# interface_b.net
KiCad netlist of a schematic drawn in EAGLE
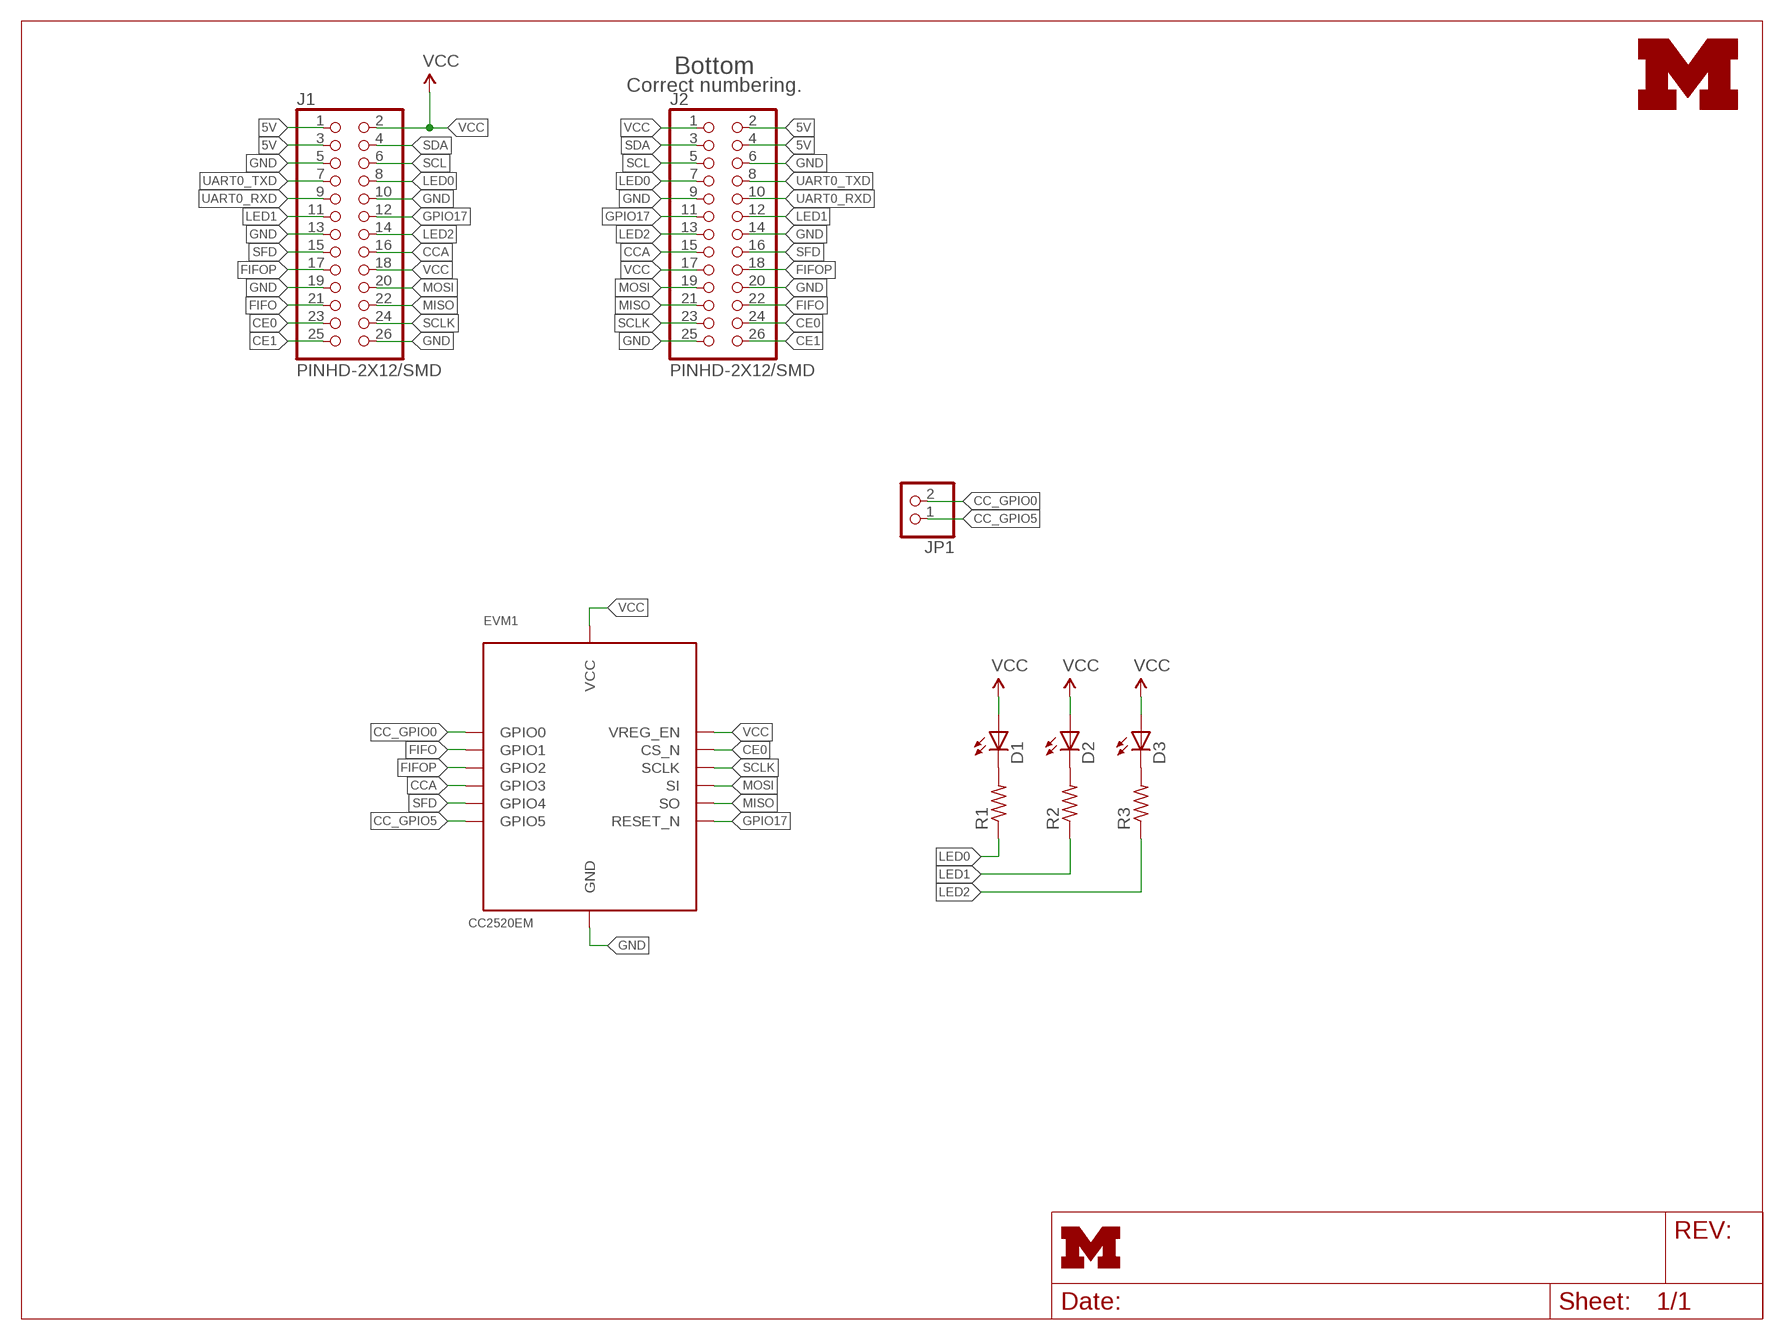
[diagram p0: schematic, sheet 1]

(export (version "E")
  (design (tool "Eeschema 10.0.6"))
  (components
    (comp (ref "D1")
      (value "LED0603")
      (footprint "eagle-import:LED-0603")
      (libsource (lib "eagle-import") (part "LED0603"))
    )
    (comp (ref "D2")
      (value "LED0603")
      (footprint "eagle-import:LED-0603")
      (libsource (lib "eagle-import") (part "LED0603"))
    )
    (comp (ref "D3")
      (value "LED0603")
      (footprint "eagle-import:LED-0603")
      (libsource (lib "eagle-import") (part "LED0603"))
    )
    (comp (ref "EVM1")
      (value "CC2520EM")
      (footprint "eagle-import:TI_CC_EVM")
      (libsource (lib "eagle-import") (part "CC2520EM"))
    )
    (comp (ref "J1")
      (value "PINHD-2X12/SMD")
      (footprint "eagle-import:2X13_SMD")
      (libsource (lib "eagle-import") (part "PINHD-2X12/SMD"))
    )
    (comp (ref "J2")
      (value "PINHD-2X12/SMD")
      (footprint "eagle-import:2X13_SMD")
      (libsource (lib "eagle-import") (part "PINHD-2X12/SMD"))
    )
    (comp (ref "JP1")
      (value "PINHD-1X2")
      (footprint "eagle-import:1X02")
      (libsource (lib "eagle-import") (part "PINHD-1X2"))
    )
    (comp (ref "R1")
      (value "R-US_R0603")
      (footprint "eagle-import:R0603")
      (libsource (lib "eagle-import") (part "R-US_R0603"))
    )
    (comp (ref "R2")
      (value "R-US_R0603")
      (footprint "eagle-import:R0603")
      (libsource (lib "eagle-import") (part "R-US_R0603"))
    )
    (comp (ref "R3")
      (value "R-US_R0603")
      (footprint "eagle-import:R0603")
      (libsource (lib "eagle-import") (part "R-US_R0603"))
    )
    (comp (ref "U$1")
      (value "UMICH_SOLID_SMALL")
      (footprint "eagle-import:UMICH_SOLID_75MIL")
      (libsource (lib "eagle-import") (part "UMICH_SOLID_SMALL"))
    )
  )
  (nets
    (net (code "1") (name "5V") (class "Default")
      (node (ref "J1") (pin "1") (pinfunction "1_1") (pintype "passive"))
      (node (ref "J1") (pin "3") (pinfunction "3_3") (pintype "passive"))
      (node (ref "J2") (pin "2") (pinfunction "2_2") (pintype "passive"))
      (node (ref "J2") (pin "4") (pinfunction "4_4") (pintype "passive"))
    )
    (net (code "2") (name "CCA") (class "Default")
      (node (ref "EVM1") (pin "P1_12") (pinfunction "GPIO3_P1_12") (pintype "bidirectional"))
      (node (ref "J1") (pin "16") (pinfunction "16_16") (pintype "passive"))
      (node (ref "J2") (pin "15") (pinfunction "15_15") (pintype "passive"))
    )
    (net (code "3") (name "CC_GPIO0") (class "Default")
      (node (ref "EVM1") (pin "P1_3") (pinfunction "GPIO0_P1_3") (pintype "bidirectional"))
      (node (ref "JP1") (pin "2") (pinfunction "2_2") (pintype "passive"))
    )
    (net (code "4") (name "CC_GPIO5") (class "Default")
      (node (ref "EVM1") (pin "P2_19") (pinfunction "GPIO5_P2_19") (pintype "bidirectional"))
      (node (ref "JP1") (pin "1") (pinfunction "1_1") (pintype "passive"))
    )
    (net (code "5") (name "CE0") (class "Default")
      (node (ref "EVM1") (pin "P1_14") (pinfunction "CS_N_P1_14") (pintype "bidirectional"))
      (node (ref "J1") (pin "23") (pinfunction "23_23") (pintype "passive"))
      (node (ref "J2") (pin "24") (pinfunction "24_24") (pintype "passive"))
    )
    (net (code "6") (name "CE1") (class "Default")
      (node (ref "J1") (pin "25") (pinfunction "25_25") (pintype "passive"))
      (node (ref "J2") (pin "26") (pinfunction "26_26") (pintype "passive"))
    )
    (net (code "7") (name "FIFO") (class "Default")
      (node (ref "EVM1") (pin "P1_7") (pinfunction "GPIO1_P1_7") (pintype "bidirectional"))
      (node (ref "J1") (pin "21") (pinfunction "21_21") (pintype "passive"))
      (node (ref "J2") (pin "22") (pinfunction "22_22") (pintype "passive"))
    )
    (net (code "8") (name "FIFOP") (class "Default")
      (node (ref "EVM1") (pin "P1_9") (pinfunction "GPIO2_P1_9") (pintype "bidirectional"))
      (node (ref "J1") (pin "17") (pinfunction "17_17") (pintype "passive"))
      (node (ref "J2") (pin "18") (pinfunction "18_18") (pintype "passive"))
    )
    (net (code "9") (name "GND") (class "Default")
      (node (ref "EVM1") (pin "P1_1") (pinfunction "GND_P1_1") (pintype "bidirectional"))
      (node (ref "EVM1") (pin "P1_19") (pinfunction "GND_P1_19") (pintype "bidirectional"))
      (node (ref "J1") (pin "10") (pinfunction "10_10") (pintype "passive"))
      (node (ref "J1") (pin "13") (pinfunction "13_13") (pintype "passive"))
      (node (ref "J1") (pin "19") (pinfunction "19_19") (pintype "passive"))
      (node (ref "J1") (pin "26") (pinfunction "26_26") (pintype "passive"))
      (node (ref "J1") (pin "5") (pinfunction "5_5") (pintype "passive"))
      (node (ref "J2") (pin "14") (pinfunction "14_14") (pintype "passive"))
      (node (ref "J2") (pin "20") (pinfunction "20_20") (pintype "passive"))
      (node (ref "J2") (pin "25") (pinfunction "25_25") (pintype "passive"))
      (node (ref "J2") (pin "6") (pinfunction "6_6") (pintype "passive"))
      (node (ref "J2") (pin "9") (pinfunction "9_9") (pintype "passive"))
    )
    (net (code "10") (name "GPIO17") (class "Default")
      (node (ref "EVM1") (pin "P2_15") (pinfunction "RESET_N_P2_15") (pintype "bidirectional"))
      (node (ref "J1") (pin "12") (pinfunction "12_12") (pintype "passive"))
      (node (ref "J2") (pin "11") (pinfunction "11_11") (pintype "passive"))
    )
    (net (code "11") (name "LED0") (class "Default")
      (node (ref "J1") (pin "8") (pinfunction "8_8") (pintype "passive"))
      (node (ref "J2") (pin "7") (pinfunction "7_7") (pintype "passive"))
      (node (ref "R1") (pin "1") (pinfunction "1_1") (pintype "passive"))
    )
    (net (code "12") (name "LED1") (class "Default")
      (node (ref "J1") (pin "11") (pinfunction "11_11") (pintype "passive"))
      (node (ref "J2") (pin "12") (pinfunction "12_12") (pintype "passive"))
      (node (ref "R2") (pin "1") (pinfunction "1_1") (pintype "passive"))
    )
    (net (code "13") (name "LED2") (class "Default")
      (node (ref "J1") (pin "14") (pinfunction "14_14") (pintype "passive"))
      (node (ref "J2") (pin "13") (pinfunction "13_13") (pintype "passive"))
      (node (ref "R3") (pin "1") (pinfunction "1_1") (pintype "passive"))
    )
    (net (code "14") (name "MISO") (class "Default")
      (node (ref "EVM1") (pin "P1_20") (pinfunction "SO_P1_20") (pintype "bidirectional"))
      (node (ref "J1") (pin "22") (pinfunction "22_22") (pintype "passive"))
      (node (ref "J2") (pin "21") (pinfunction "21_21") (pintype "passive"))
    )
    (net (code "15") (name "MOSI") (class "Default")
      (node (ref "EVM1") (pin "P1_18") (pinfunction "SI_P1_18") (pintype "bidirectional"))
      (node (ref "J1") (pin "20") (pinfunction "20_20") (pintype "passive"))
      (node (ref "J2") (pin "19") (pinfunction "19_19") (pintype "passive"))
    )
    (net (code "16") (name "Net-(D1-PadC)") (class "Default")
      (node (ref "D1") (pin "C") (pinfunction "C_C") (pintype "passive"))
      (node (ref "R1") (pin "2") (pinfunction "2_2") (pintype "passive"))
    )
    (net (code "17") (name "Net-(D2-PadC)") (class "Default")
      (node (ref "D2") (pin "C") (pinfunction "C_C") (pintype "passive"))
      (node (ref "R2") (pin "2") (pinfunction "2_2") (pintype "passive"))
    )
    (net (code "18") (name "Net-(D3-PadC)") (class "Default")
      (node (ref "D3") (pin "C") (pinfunction "C_C") (pintype "passive"))
      (node (ref "R3") (pin "2") (pinfunction "2_2") (pintype "passive"))
    )
    (net (code "19") (name "SCL") (class "Default")
      (node (ref "J1") (pin "6") (pinfunction "6_6") (pintype "passive"))
      (node (ref "J2") (pin "5") (pinfunction "5_5") (pintype "passive"))
    )
    (net (code "20") (name "SCLK") (class "Default")
      (node (ref "EVM1") (pin "P1_16") (pinfunction "SCLK_P1_16") (pintype "bidirectional"))
      (node (ref "J1") (pin "24") (pinfunction "24_24") (pintype "passive"))
      (node (ref "J2") (pin "23") (pinfunction "23_23") (pintype "passive"))
    )
    (net (code "21") (name "SDA") (class "Default")
      (node (ref "J1") (pin "4") (pinfunction "4_4") (pintype "passive"))
      (node (ref "J2") (pin "3") (pinfunction "3_3") (pintype "passive"))
    )
    (net (code "22") (name "SFD") (class "Default")
      (node (ref "EVM1") (pin "P2_18") (pinfunction "GPIO4_P2_18") (pintype "bidirectional"))
      (node (ref "J1") (pin "15") (pinfunction "15_15") (pintype "passive"))
      (node (ref "J2") (pin "16") (pinfunction "16_16") (pintype "passive"))
    )
    (net (code "23") (name "UART0_RXD") (class "Default")
      (node (ref "J1") (pin "9") (pinfunction "9_9") (pintype "passive"))
      (node (ref "J2") (pin "10") (pinfunction "10_10") (pintype "passive"))
    )
    (net (code "24") (name "UART0_TXD") (class "Default")
      (node (ref "J1") (pin "7") (pinfunction "7_7") (pintype "passive"))
      (node (ref "J2") (pin "8") (pinfunction "8_8") (pintype "passive"))
    )
    (net (code "25") (name "VCC") (class "Default")
      (node (ref "D1") (pin "A") (pinfunction "A_A") (pintype "passive"))
      (node (ref "D2") (pin "A") (pinfunction "A_A") (pintype "passive"))
      (node (ref "D3") (pin "A") (pinfunction "A_A") (pintype "passive"))
      (node (ref "EVM1") (pin "P1_10") (pinfunction "VREG_EN_P1_10") (pintype "bidirectional"))
      (node (ref "EVM1") (pin "P2_7") (pinfunction "VCC_P2_7") (pintype "bidirectional"))
      (node (ref "EVM1") (pin "P2_9") (pinfunction "VCC_P2_9") (pintype "bidirectional"))
      (node (ref "J1") (pin "18") (pinfunction "18_18") (pintype "passive"))
      (node (ref "J1") (pin "2") (pinfunction "2_2") (pintype "passive"))
      (node (ref "J2") (pin "1") (pinfunction "1_1") (pintype "passive"))
      (node (ref "J2") (pin "17") (pinfunction "17_17") (pintype "passive"))
    )
  )
)
